# Interface_2_SCH.net
KiCad netlist of a schematic drawn in Altium Designer
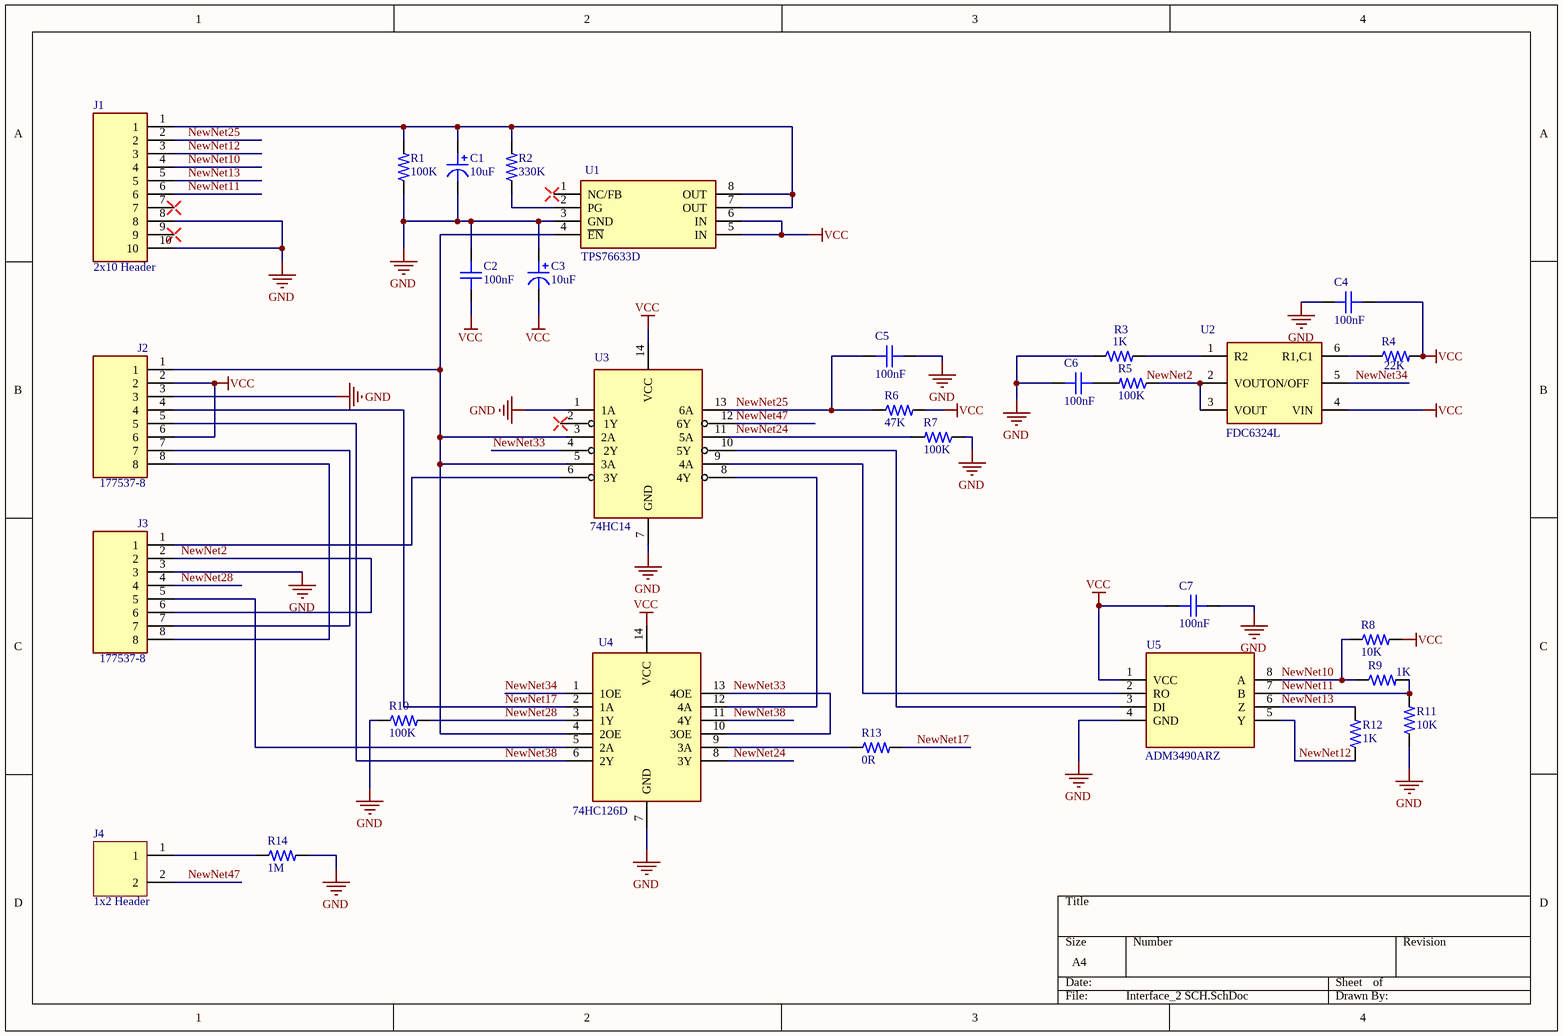
[diagram p0: Interface_2 SCH.SchDoc]

(export (version "E")
  (design (tool "Eeschema 10.0.6"))
  (components
    (comp (ref "C1")
      (value "10uF")
      (footprint "CASE-B")
      (description "Cap Tant Solid 10uF 4V A CASE 20% (3.2 X 1.6 X 1.6mm) SMD 3216-18 5.1 Ohm 125C T/R")
      (fields
        (field (name "MANUFACTURER PART NUMBER") "293D106X0004A2TE3")
        (field (name "MANUFACTURER") "Vishay Sprague")
      )
      (libsource (lib "Database_Libs2") (part "Capacitor - Polarised Capacitor"))
    )
    (comp (ref "C2")
      (value "100nF")
      (footprint "CAPC2012X14N(0805)")
      (description "Cap Ceramic 0.1uF 16V X7R 10% SMD 0805 FlexiTerm 125°C Paper T/R")
      (fields (field (name "MANUFACTURER PART NUMBER") "0805YC104K4Z2A") (field (name "MANUFACTURER") "AVX"))
      (libsource (lib "Database_Libs2") (part "Capacitor - Non-Polarised Capacitor"))
    )
    (comp (ref "C3")
      (value "10uF")
      (footprint "CASE-B")
      (description "Cap Tant Solid 10uF 4V A CASE 20% (3.2 X 1.6 X 1.6mm) SMD 3216-18 5.1 Ohm 125C T/R")
      (fields
        (field (name "MANUFACTURER PART NUMBER") "293D106X0004A2TE3")
        (field (name "MANUFACTURER") "Vishay Sprague")
      )
      (libsource (lib "Database_Libs2") (part "Capacitor - Polarised Capacitor"))
    )
    (comp (ref "C4")
      (value "100nF")
      (footprint "CAPC2012X14N(0805)")
      (description "Cap Ceramic 0.1uF 16V X7R 10% SMD 0805 FlexiTerm 125°C Paper T/R")
      (fields (field (name "MANUFACTURER PART NUMBER") "0805YC104K4Z2A") (field (name "MANUFACTURER") "AVX"))
      (libsource (lib "Database_Libs2") (part "Capacitor - Non-Polarised Capacitor"))
    )
    (comp (ref "C5")
      (value "100nF")
      (footprint "CAPC2012X14N(0805)")
      (description "Cap Ceramic 0.1uF 16V X7R 10% SMD 0805 FlexiTerm 125°C Paper T/R")
      (fields (field (name "MANUFACTURER PART NUMBER") "0805YC104K4Z2A") (field (name "MANUFACTURER") "AVX"))
      (libsource (lib "Database_Libs2") (part "Capacitor - Non-Polarised Capacitor"))
    )
    (comp (ref "C6")
      (value "100nF")
      (footprint "CAPC2012X14N(0805)")
      (description "Cap Ceramic 0.1uF 16V X7R 10% SMD 0805 FlexiTerm 125°C Paper T/R")
      (fields (field (name "MANUFACTURER PART NUMBER") "0805YC104K4Z2A") (field (name "MANUFACTURER") "AVX"))
      (libsource (lib "Database_Libs2") (part "Capacitor - Non-Polarised Capacitor"))
    )
    (comp (ref "C7")
      (value "100nF")
      (footprint "CAPC2012X14N(0805)")
      (description "Cap Ceramic 0.1uF 16V X7R 10% SMD 0805 FlexiTerm 125°C Paper T/R")
      (fields (field (name "MANUFACTURER PART NUMBER") "0805YC104K4Z2A") (field (name "MANUFACTURER") "AVX"))
      (libsource (lib "Database_Libs2") (part "Capacitor - Non-Polarised Capacitor"))
    )
    (comp (ref "J1")
      (value "2x10 Header")
      (footprint "HEADER-2x10H")
      (description "Headers & Wire Housings 2X10P AMPMODU II STIFTLEI")
      (fields (field (name "MP") "1-1241164-0") (field (name "MF") "TE Connectivity"))
      (libsource (lib "Database_Libs2") (part "2x10 Header"))
    )
    (comp (ref "J2")
      (value "177537-8")
      (footprint "HEADER-1X8H")
      (fields (field (name "MANUFACTURER PART NUMBER") "90120-0928") (field (name "MANUFACTURER") "Molex"))
      (libsource (lib "Database_Libs2") (part "1x8 Header"))
    )
    (comp (ref "J3")
      (value "177537-8")
      (footprint "HEADER-1X8H")
      (fields (field (name "MANUFACTURER PART NUMBER") "90120-0928") (field (name "MANUFACTURER") "Molex"))
      (libsource (lib "Database_Libs2") (part "1x8 Header"))
    )
    (comp (ref "J4")
      (value "1x2 Header")
      (footprint "HEADER-1X2H")
      (description "TERM BLOCK HDR 2POS VERT 5.08MM")
      (fields
        (field (name "MANUFACTURER PART NUMBER") "OSTOQ025450")
        (field (name "MANUFACTURER") "On-Shore Technology")
      )
      (libsource (lib "Database_Libs2") (part "1x2 Header"))
    )
    (comp (ref "R1")
      (value "100K")
      (footprint "RESC2013X70N(0805)")
      (description "Res Thin Film 0805 100K Ohm 0.1% 0.125W(1/8W) ±10ppm/C Molded SMD Paper T/R")
      (fields
        (field (name "MANUFACTURER PART NUMBER") "RT0805BRB07100KL")
        (field (name "MANUFACTURER") "Yageo")
      )
      (libsource (lib "Database_Libs2") (part "Resistor"))
    )
    (comp (ref "R2")
      (value "330K")
      (footprint "RESC2013X70N(0805)")
      (description "Res Thick Film 0805 330K Ohm 5% 0.125W(1/8W) ±100ppm/C Molded SMD T/R")
      (fields
        (field (name "MANUFACTURER PART NUMBER") "RC2012J334CS")
        (field (name "MANUFACTURER") "Samsung")
      )
      (libsource (lib "Database_Libs2") (part "Resistor"))
    )
    (comp (ref "R3")
      (value "1K")
      (footprint "RESC2013X70N(0805)")
      (description "Res Thick Film 0805 1K Ohm 1% 0.125W(1/8W) ±100ppm/C Pad SMD Automotive T/R")
      (fields
        (field (name "MANUFACTURER PART NUMBER") "CRCW08051K00FKEA")
        (field (name "MANUFACTURER") "Vishay Dale")
      )
      (libsource (lib "Database_Libs2") (part "Resistor"))
    )
    (comp (ref "R4")
      (value "22K")
      (footprint "RESC2013X70N(0805)")
      (description "Res Thick Film 0805 22K Ohm 5% 0.125W(1/8W) ±100ppm/C Molded SMD T/R")
      (fields
        (field (name "MANUFACTURER PART NUMBER") "RC2012J223CS")
        (field (name "MANUFACTURER") "Samsung")
      )
      (libsource (lib "Database_Libs2") (part "Resistor"))
    )
    (comp (ref "R5")
      (value "100K")
      (footprint "RESC2013X70N(0805)")
      (description "Res Thin Film 0805 100K Ohm 0.1% 0.125W(1/8W) ±10ppm/C Molded SMD Paper T/R")
      (fields
        (field (name "MANUFACTURER PART NUMBER") "RT0805BRB07100KL")
        (field (name "MANUFACTURER") "Yageo")
      )
      (libsource (lib "Database_Libs2") (part "Resistor"))
    )
    (comp (ref "R6")
      (value "47K")
      (footprint "RESC2013X70N(0805)")
      (description "Res Thick Film 0805 47K Ohm 1% 1/8W 100ppm/C Molded SMD Paper T/R")
      (fields
        (field (name "MANUFACTURER PART NUMBER") "RC0805FR-0747KL")
        (field (name "MANUFACTURER") "Yageo")
      )
      (libsource (lib "Database_Libs2") (part "Resistor"))
    )
    (comp (ref "R7")
      (value "100K")
      (footprint "RESC2013X70N(0805)")
      (description "Res Thin Film 0805 100K Ohm 0.1% 0.125W(1/8W) ±10ppm/C Molded SMD Paper T/R")
      (fields
        (field (name "MANUFACTURER PART NUMBER") "RT0805BRB07100KL")
        (field (name "MANUFACTURER") "Yageo")
      )
      (libsource (lib "Database_Libs2") (part "Resistor"))
    )
    (comp (ref "R8")
      (value "10K")
      (footprint "RESC2013X70N(0805)")
      (description "Res Thick Film 0805 10K Ohm 1% 0.33W(1/3W) ±100ppm/C Molded SMD Automotive Paper T/R")
      (fields
        (field (name "MANUFACTURER PART NUMBER") "CRCW080510K0FKEAHP")
        (field (name "MANUFACTURER") "Vishay")
      )
      (libsource (lib "Database_Libs2") (part "Resistor"))
    )
    (comp (ref "R9")
      (value "1K")
      (footprint "RESC2013X70N(0805)")
      (description "Res Thick Film 0805 1K Ohm 1% 0.125W(1/8W) ±100ppm/C Pad SMD Automotive T/R")
      (fields
        (field (name "MANUFACTURER PART NUMBER") "CRCW08051K00FKEA")
        (field (name "MANUFACTURER") "Vishay Dale")
      )
      (libsource (lib "Database_Libs2") (part "Resistor"))
    )
    (comp (ref "R10")
      (value "100K")
      (footprint "RESC2013X70N(0805)")
      (description "Res Thin Film 0805 100K Ohm 0.1% 0.125W(1/8W) ±10ppm/C Molded SMD Paper T/R")
      (fields
        (field (name "MANUFACTURER PART NUMBER") "RT0805BRB07100KL")
        (field (name "MANUFACTURER") "Yageo")
      )
      (libsource (lib "Database_Libs2") (part "Resistor"))
    )
    (comp (ref "R11")
      (value "10K")
      (footprint "RESC2013X70N(0805)")
      (description "Res Thick Film 0805 10K Ohm 1% 0.33W(1/3W) ±100ppm/C Molded SMD Automotive Paper T/R")
      (fields
        (field (name "MANUFACTURER PART NUMBER") "CRCW080510K0FKEAHP")
        (field (name "MANUFACTURER") "Vishay")
      )
      (libsource (lib "Database_Libs2") (part "Resistor"))
    )
    (comp (ref "R12")
      (value "1K")
      (footprint "RESC2013X70N(0805)")
      (description "Res Thick Film 0805 1K Ohm 1% 0.125W(1/8W) ±100ppm/C Pad SMD Automotive T/R")
      (fields
        (field (name "MANUFACTURER PART NUMBER") "CRCW08051K00FKEA")
        (field (name "MANUFACTURER") "Vishay Dale")
      )
      (libsource (lib "Database_Libs2") (part "Resistor"))
    )
    (comp (ref "R13")
      (value "0R")
      (footprint "RESC2013X70N(0805)")
      (description "Res Thick Film 0805100K SMD Automotive T/R")
      (fields
        (field (name "MANUFACTURER PART NUMBER") "CRCW08050000Z0EB")
        (field (name "MANUFACTURER") "Vishay Dale")
      )
      (libsource (lib "Database_Libs2") (part "Resistor"))
    )
    (comp (ref "R14")
      (value "1M")
      (footprint "RESC2013X70N(0805)")
      (description "Res Thick Film 0805 1M Ohm 5% 1/4W 200ppm/C Molded SMD SMD Punched Carrier T/R")
      (fields
        (field (name "MANUFACTURER PART NUMBER") "ERJ-P06J105V")
        (field (name "MANUFACTURER") "Panasonic")
      )
      (libsource (lib "Database_Libs2") (part "Resistor"))
    )
    (comp (ref "U1")
      (value "TPS76633D")
      (footprint "SOIC-8")
      (description "IC REG LINEAR 3.3V 250MA 8SOIC")
      (fields
        (field (name "MANUFACTURER PART NUMBER") "TPS76633DG4")
        (field (name "MANUFACTURER") "Texas Instruments")
      )
      (libsource (lib "Database_Libs2") (part "TPS76633"))
    )
    (comp (ref "U2")
      (value "FDC6324L")
      (footprint "SUPERSOT-6")
      (description "IC LOAD SWITCH INT 20VIN SSOT-6")
      (fields (field (name "MANUFACTURER") "ON Semiconductor / Fairchild"))
      (libsource (lib "Database_Libs2") (part "FDC6324L"))
    )
    (comp (ref "U3")
      (value "74HC14")
      (footprint "SO-14")
      (description "IC, HEX INVERTER, SCHMITT TRIGGER SOIC14")
      (fields (field (name "MP") "74ACT14SCX") (field (name "MF") "ON Semiconductor"))
      (libsource (lib "Database_Libs2") (part "74HC14"))
    )
    (comp (ref "U4")
      (value "74HC126D")
      (footprint "SO-14")
      (description "Buffer/Line Driver 4-CH Non-Inverting 3-ST CMOS 14-Pin SO T/R")
      (fields
        (field (name "MF") "Toshiba Semiconductor")
        (field (name "MANUFACTURER PART NUMBER") "74HC126D-Q100J")
      )
      (libsource (lib "Database_Libs2") (part "74HC126D"))
    )
    (comp (ref "U5")
      (value "ADM3490ARZ")
      (footprint "SOIC-8")
      (description "Single Transmitter/Receiver RS-422/RS-485 8-Pin SOIC N Tube")
      (fields (field (name "MF") "Analog Devices"))
      (libsource (lib "Database_Libs2") (part "ADM3490ARZ"))
    )
  )
  (nets
    (net (code "1") (name "/NewNet2") (class "Default")
      (node (ref "J3") (pin "2") (pinfunction "2_2") (pintype "passive"))
      (node (ref "J3") (pin "6") (pinfunction "6_6") (pintype "passive"))
    )
    (net (code "2") (name "/NewNet10") (class "Default")
      (node (ref "J1") (pin "4") (pinfunction "4_4") (pintype "passive"))
      (node (ref "R8") (pin "1") (pinfunction "1_1") (pintype "passive"))
      (node (ref "R9") (pin "1") (pinfunction "1_1") (pintype "passive"))
      (node (ref "U5") (pin "8") (pinfunction "A_8") (pintype "passive"))
    )
    (net (code "3") (name "/NewNet11") (class "Default")
      (node (ref "J1") (pin "6") (pinfunction "6_6") (pintype "passive"))
      (node (ref "R11") (pin "2") (pinfunction "2_2") (pintype "passive"))
      (node (ref "R9") (pin "2") (pinfunction "2_2") (pintype "passive"))
      (node (ref "U5") (pin "7") (pinfunction "B_7") (pintype "passive"))
    )
    (net (code "4") (name "/NewNet12") (class "Default")
      (node (ref "J1") (pin "3") (pinfunction "3_3") (pintype "passive"))
      (node (ref "R12") (pin "1") (pinfunction "1_1") (pintype "passive"))
      (node (ref "U5") (pin "5") (pinfunction "Y_5") (pintype "passive"))
    )
    (net (code "5") (name "/NewNet13") (class "Default")
      (node (ref "J1") (pin "5") (pinfunction "5_5") (pintype "passive"))
      (node (ref "R12") (pin "2") (pinfunction "2_2") (pintype "passive"))
      (node (ref "U5") (pin "6") (pinfunction "Z_6") (pintype "passive"))
    )
    (net (code "6") (name "/NewNet17") (class "Default")
      (node (ref "J2") (pin "4") (pinfunction "4_4") (pintype "passive"))
      (node (ref "R13") (pin "2") (pinfunction "2_2") (pintype "passive"))
      (node (ref "U4") (pin "2") (pinfunction "1A_2") (pintype "passive"))
    )
    (net (code "7") (name "/NewNet24") (class "Default")
      (node (ref "R7") (pin "2") (pinfunction "2_2") (pintype "passive"))
      (node (ref "U3") (pin "11") (pinfunction "5A_11") (pintype "passive"))
      (node (ref "U4") (pin "8") (pinfunction "3Y_8") (pintype "passive"))
    )
    (net (code "8") (name "/NewNet25") (class "Default")
      (node (ref "C5") (pin "2") (pinfunction "2_2") (pintype "passive"))
      (node (ref "J1") (pin "2") (pinfunction "2_2") (pintype "passive"))
      (node (ref "R6") (pin "1") (pinfunction "1_1") (pintype "passive"))
      (node (ref "U3") (pin "13") (pinfunction "6A_13") (pintype "passive"))
    )
    (net (code "9") (name "/NewNet28") (class "Default")
      (node (ref "J3") (pin "4") (pinfunction "4_4") (pintype "passive"))
      (node (ref "R10") (pin "2") (pinfunction "2_2") (pintype "passive"))
      (node (ref "U4") (pin "3") (pinfunction "1Y_3") (pintype "passive"))
    )
    (net (code "10") (name "/NewNet33") (class "Default")
      (node (ref "U3") (pin "4") (pinfunction "2Y_4") (pintype "passive"))
      (node (ref "U4") (pin "10") (pinfunction "3OE_10") (pintype "passive"))
      (node (ref "U4") (pin "13") (pinfunction "4OE_13") (pintype "passive"))
    )
    (net (code "11") (name "/NewNet34") (class "Default")
      (node (ref "U2") (pin "5") (pintype "passive"))
      (node (ref "U4") (pin "1") (pinfunction "1OE_1") (pintype "passive"))
    )
    (net (code "12") (name "/NewNet38") (class "Default")
      (node (ref "J2") (pin "5") (pinfunction "5_5") (pintype "passive"))
      (node (ref "U4") (pin "11") (pinfunction "4Y_11") (pintype "passive"))
      (node (ref "U4") (pin "6") (pinfunction "2Y_6") (pintype "passive"))
    )
    (net (code "13") (name "/NewNet47") (class "Default")
      (node (ref "J4") (pin "2") (pinfunction "2_2") (pintype "passive"))
      (node (ref "U3") (pin "12") (pinfunction "6Y_12") (pintype "passive"))
    )
    (net (code "14") (name "GND") (class "Default")
      (node (ref "C1") (pin "2") (pinfunction "2_2") (pintype "passive"))
      (node (ref "C2") (pin "2") (pinfunction "2_2") (pintype "passive"))
      (node (ref "C3") (pin "1") (pinfunction "1_1") (pintype "passive"))
      (node (ref "C4") (pin "2") (pinfunction "2_2") (pintype "passive"))
      (node (ref "C5") (pin "1") (pinfunction "1_1") (pintype "passive"))
      (node (ref "C6") (pin "2") (pinfunction "2_2") (pintype "passive"))
      (node (ref "C7") (pin "1") (pinfunction "1_1") (pintype "passive"))
      (node (ref "J1") (pin "10") (pinfunction "10_10") (pintype "passive"))
      (node (ref "J1") (pin "8") (pinfunction "8_8") (pintype "passive"))
      (node (ref "J2") (pin "3") (pinfunction "3_3") (pintype "passive"))
      (node (ref "J3") (pin "3") (pinfunction "3_3") (pintype "passive"))
      (node (ref "R1") (pin "1") (pinfunction "1_1") (pintype "passive"))
      (node (ref "R10") (pin "1") (pinfunction "1_1") (pintype "passive"))
      (node (ref "R11") (pin "1") (pinfunction "1_1") (pintype "passive"))
      (node (ref "R14") (pin "2") (pinfunction "2_2") (pintype "passive"))
      (node (ref "R3") (pin "1") (pinfunction "1_1") (pintype "passive"))
      (node (ref "R7") (pin "1") (pinfunction "1_1") (pintype "passive"))
      (node (ref "U1") (pin "3") (pinfunction "GND_3") (pintype "passive"))
      (node (ref "U3") (pin "1") (pinfunction "1A_1") (pintype "passive"))
      (node (ref "U3") (pin "7") (pinfunction "GND_7") (pintype "passive"))
      (node (ref "U4") (pin "7") (pinfunction "GND_7") (pintype "passive"))
      (node (ref "U5") (pin "4") (pinfunction "GND_4") (pintype "passive"))
    )
    (net (code "15") (name "Net-(C1-Pad1)") (class "Default")
      (node (ref "C1") (pin "1") (pinfunction "1_1") (pintype "passive"))
      (node (ref "J1") (pin "1") (pinfunction "1_1") (pintype "passive"))
      (node (ref "R1") (pin "2") (pinfunction "2_2") (pintype "passive"))
      (node (ref "R2") (pin "2") (pinfunction "2_2") (pintype "passive"))
      (node (ref "U1") (pin "7") (pinfunction "OUT_7") (pintype "passive"))
      (node (ref "U1") (pin "8") (pinfunction "OUT_8") (pintype "passive"))
    )
    (net (code "16") (name "Net-(C6-Pad1)") (class "Default")
      (node (ref "C6") (pin "1") (pinfunction "1_1") (pintype "passive"))
      (node (ref "R5") (pin "2") (pinfunction "2_2") (pintype "passive"))
    )
    (net (code "17") (name "Net-(J2-Pad7)") (class "Default")
      (node (ref "J2") (pin "7") (pinfunction "7_7") (pintype "passive"))
      (node (ref "J3") (pin "7") (pinfunction "7_7") (pintype "passive"))
    )
    (net (code "18") (name "Net-(J2-Pad8)") (class "Default")
      (node (ref "J2") (pin "8") (pinfunction "8_8") (pintype "passive"))
      (node (ref "J3") (pin "8") (pinfunction "8_8") (pintype "passive"))
    )
    (net (code "19") (name "Net-(J4-Pad1)") (class "Default")
      (node (ref "J4") (pin "1") (pinfunction "1_1") (pintype "passive"))
      (node (ref "R14") (pin "1") (pinfunction "1_1") (pintype "passive"))
    )
    (net (code "20") (name "Net-(U1-PG)") (class "Default")
      (node (ref "R2") (pin "1") (pinfunction "1_1") (pintype "passive"))
      (node (ref "U1") (pin "2") (pinfunction "PG_2") (pintype "passive"))
    )
    (net (code "21") (name "Net-(U1-~{EN})") (class "Default")
      (node (ref "J2") (pin "1") (pinfunction "1_1") (pintype "passive"))
      (node (ref "U1") (pin "4") (pinfunction "~{EN}_4") (pintype "power_in"))
      (node (ref "U3") (pin "3") (pinfunction "2A_3") (pintype "passive"))
      (node (ref "U3") (pin "5") (pinfunction "3A_5") (pintype "passive"))
      (node (ref "U4") (pin "4") (pinfunction "2OE_4") (pintype "passive"))
    )
    (net (code "22") (name "Net-(U2-R1,C1)") (class "Default")
      (node (ref "R4") (pin "1") (pinfunction "1_1") (pintype "passive"))
      (node (ref "U2") (pin "6") (pinfunction "R1,C1_6") (pintype "passive"))
    )
    (net (code "23") (name "Net-(U2-R2)") (class "Default")
      (node (ref "R3") (pin "2") (pinfunction "2_2") (pintype "passive"))
      (node (ref "U2") (pin "1") (pinfunction "R2_1") (pintype "passive"))
    )
    (net (code "24") (name "Net-(U2-VOUT)") (class "Default")
      (node (ref "R5") (pin "1") (pinfunction "1_1") (pintype "passive"))
      (node (ref "U2") (pin "2") (pinfunction "VOUTON/OFF_2") (pintype "passive"))
      (node (ref "U2") (pin "3") (pinfunction "VOUT_3") (pintype "passive"))
    )
    (net (code "25") (name "Net-(U3-3Y)") (class "Default")
      (node (ref "J3") (pin "1") (pinfunction "1_1") (pintype "passive"))
      (node (ref "U3") (pin "6") (pinfunction "3Y_6") (pintype "passive"))
    )
    (net (code "26") (name "Net-(U3-4A)") (class "Default")
      (node (ref "U3") (pin "9") (pinfunction "4A_9") (pintype "passive"))
      (node (ref "U5") (pin "2") (pinfunction "RO_2") (pintype "passive"))
    )
    (net (code "27") (name "Net-(U3-4Y)") (class "Default")
      (node (ref "U3") (pin "8") (pinfunction "4Y_8") (pintype "passive"))
      (node (ref "U4") (pin "12") (pinfunction "4A_12") (pintype "passive"))
    )
    (net (code "28") (name "Net-(U3-5Y)") (class "Default")
      (node (ref "U3") (pin "10") (pinfunction "5Y_10") (pintype "passive"))
      (node (ref "U5") (pin "3") (pinfunction "DI_3") (pintype "passive"))
    )
    (net (code "29") (name "Net-(U4-2A)") (class "Default")
      (node (ref "J3") (pin "5") (pinfunction "5_5") (pintype "passive"))
      (node (ref "U4") (pin "5") (pinfunction "2A_5") (pintype "passive"))
    )
    (net (code "30") (name "Net-(U4-3A)") (class "Default")
      (node (ref "R13") (pin "1") (pinfunction "1_1") (pintype "passive"))
      (node (ref "U4") (pin "9") (pinfunction "3A_9") (pintype "passive"))
    )
    (net (code "31") (name "VCC") (class "Default")
      (node (ref "C2") (pin "1") (pinfunction "1_1") (pintype "passive"))
      (node (ref "C3") (pin "2") (pinfunction "2_2") (pintype "passive"))
      (node (ref "C4") (pin "1") (pinfunction "1_1") (pintype "passive"))
      (node (ref "C7") (pin "2") (pinfunction "2_2") (pintype "passive"))
      (node (ref "J2") (pin "2") (pinfunction "2_2") (pintype "passive"))
      (node (ref "J2") (pin "6") (pinfunction "6_6") (pintype "passive"))
      (node (ref "R4") (pin "2") (pinfunction "2_2") (pintype "passive"))
      (node (ref "R6") (pin "2") (pinfunction "2_2") (pintype "passive"))
      (node (ref "R8") (pin "2") (pinfunction "2_2") (pintype "passive"))
      (node (ref "U1") (pin "5") (pinfunction "IN_5") (pintype "passive"))
      (node (ref "U1") (pin "6") (pinfunction "IN_6") (pintype "passive"))
      (node (ref "U2") (pin "4") (pinfunction "VIN_4") (pintype "power_in"))
      (node (ref "U3") (pin "14") (pinfunction "VCC_14") (pintype "power_in"))
      (node (ref "U4") (pin "14") (pinfunction "VCC_14") (pintype "power_in"))
      (node (ref "U5") (pin "1") (pinfunction "VCC_1") (pintype "passive"))
    )
    (net (code "32") (name "unconnected-(J1-Pad7)") (class "Default")
      (node (ref "J1") (pin "7") (pinfunction "7_7") (pintype "passive"))
    )
    (net (code "33") (name "unconnected-(J1-Pad9)") (class "Default")
      (node (ref "J1") (pin "9") (pinfunction "9_9") (pintype "passive"))
    )
    (net (code "34") (name "unconnected-(U1-NC{slash}FB-Pad1)") (class "Default")
      (node (ref "U1") (pin "1") (pinfunction "NC/FB_1") (pintype "passive"))
    )
    (net (code "35") (name "unconnected-(U3-1Y-Pad2)") (class "Default")
      (node (ref "U3") (pin "2") (pinfunction "1Y_2") (pintype "passive"))
    )
  )
)
